# schematic.net
KiCad netlist of a schematic drawn in EAGLE
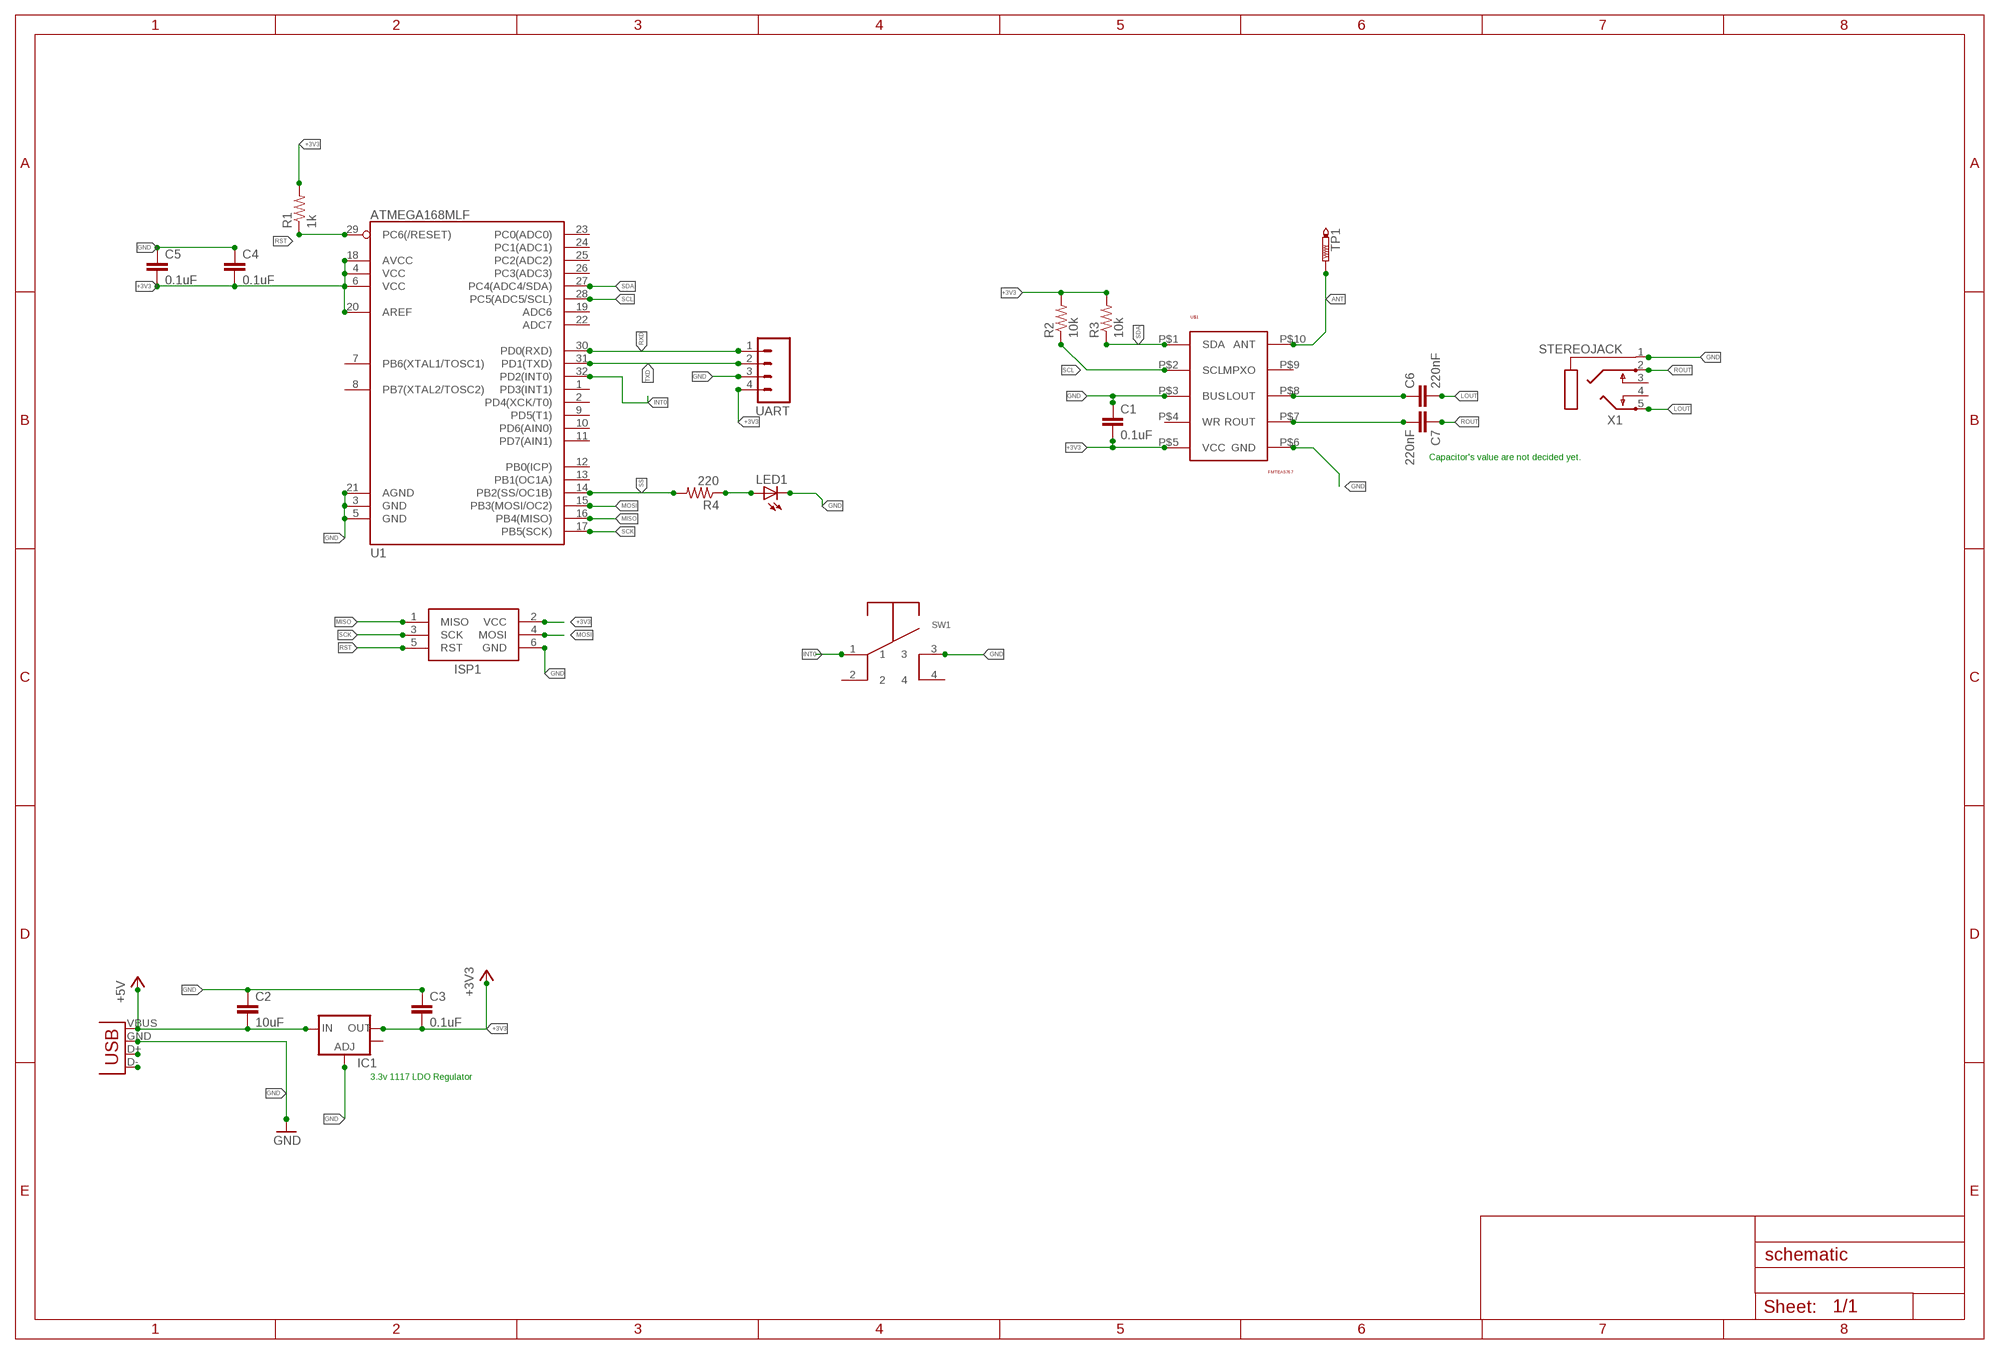
[diagram p0: schematic, sheet 1]

(export (version "E")
  (design (tool "Eeschema 10.0.6"))
  (components
    (comp (ref "C1")
      (value "0.1uF")
      (footprint "eagle-import:0402-CAP")
      (libsource (lib "eagle-import") (part "CAP0402-CAP"))
    )
    (comp (ref "C2")
      (value "10uF")
      (footprint "eagle-import:0402-CAP")
      (libsource (lib "eagle-import") (part "CAP0402-CAP"))
    )
    (comp (ref "C3")
      (value "0.1uF")
      (footprint "eagle-import:0402-CAP")
      (libsource (lib "eagle-import") (part "CAP0402-CAP"))
    )
    (comp (ref "C4")
      (value "0.1uF")
      (footprint "eagle-import:0402-CAP")
      (libsource (lib "eagle-import") (part "CAP0402-CAP"))
    )
    (comp (ref "C5")
      (value "0.1uF")
      (footprint "eagle-import:0402-CAP")
      (libsource (lib "eagle-import") (part "CAP0402-CAP"))
    )
    (comp (ref "C6")
      (value "220nF")
      (footprint "eagle-import:0402-CAP")
      (libsource (lib "eagle-import") (part "CAP0402-CAP"))
    )
    (comp (ref "C7")
      (value "220nF")
      (footprint "eagle-import:0402-CAP")
      (libsource (lib "eagle-import") (part "CAP0402-CAP"))
    )
    (comp (ref "IC1")
      (value "V_REG_LM1117SOT223")
      (footprint "eagle-import:SOT223")
      (libsource (lib "eagle-import") (part "V_REG_LM1117SOT223"))
    )
    (comp (ref "ISP1")
      (value "AVRISP-6")
      (footprint "eagle-import:AVRISP")
      (libsource (lib "eagle-import") (part "AVRISP-6"))
    )
    (comp (ref "JP1")
      (value "USB-A-H")
      (footprint "eagle-import:USB-A-H")
      (libsource (lib "eagle-import") (part "USB-A-H"))
    )
    (comp (ref "LED1")
      (value "LEDCHIPLED_0603")
      (footprint "eagle-import:CHIPLED_0603")
      (libsource (lib "eagle-import") (part "LEDCHIPLED_0603"))
    )
    (comp (ref "R1")
      (value "1k")
      (footprint "eagle-import:0402-RES")
      (libsource (lib "eagle-import") (part "RESISTOR0402-RES"))
    )
    (comp (ref "R2")
      (value "10k")
      (footprint "eagle-import:0402-RES")
      (libsource (lib "eagle-import") (part "RESISTOR0402-RES"))
    )
    (comp (ref "R3")
      (value "10k")
      (footprint "eagle-import:0402-RES")
      (libsource (lib "eagle-import") (part "RESISTOR0402-RES"))
    )
    (comp (ref "R4")
      (value "220")
      (footprint "eagle-import:0402-RES")
      (libsource (lib "eagle-import") (part "RESISTOR0402-RES"))
    )
    (comp (ref "SW1")
      (value "TAC-SOFT")
      (footprint "eagle-import:SWITCH_SMD")
      (libsource (lib "eagle-import") (part "TAC-SOFT"))
    )
    (comp (ref "TP1")
      (value "PTR1TP20SQ")
      (footprint "eagle-import:TP20SQ")
      (libsource (lib "eagle-import") (part "PTR1TP20SQ"))
    )
    (comp (ref "U$1")
      (value "FMTEA5767")
      (footprint "eagle-import:FMTEA5767")
      (libsource (lib "eagle-import") (part "FMTEA5767"))
    )
    (comp (ref "U1")
      (value "ATMEGA168MLF")
      (footprint "eagle-import:MLF32")
      (libsource (lib "eagle-import") (part "ATMEGA168MLF"))
    )
    (comp (ref "UART")
      (value "M04PTH")
      (footprint "eagle-import:1X04")
      (libsource (lib "eagle-import") (part "M04PTH"))
    )
    (comp (ref "X1")
      (value "STEREOJACK")
      (footprint "eagle-import:STX3100")
      (libsource (lib "eagle-import") (part "STEREOJACK"))
    )
  )
  (nets
    (net (code "1") (name "+3V3") (class "Default")
      (node (ref "C1") (pin "2") (pinfunction "2_2") (pintype "passive"))
      (node (ref "C3") (pin "2") (pinfunction "2_2") (pintype "passive"))
      (node (ref "C4") (pin "2") (pinfunction "2_2") (pintype "passive"))
      (node (ref "C5") (pin "2") (pinfunction "2_2") (pintype "passive"))
      (node (ref "IC1") (pin "2") (pinfunction "OUT_2") (pintype "output"))
      (node (ref "ISP1") (pin "2") (pinfunction "VCC_2") (pintype "power_in"))
      (node (ref "R1") (pin "2") (pinfunction "2_2") (pintype "passive"))
      (node (ref "R2") (pin "2") (pinfunction "2_2") (pintype "passive"))
      (node (ref "R3") (pin "2") (pinfunction "2_2") (pintype "passive"))
      (node (ref "U$1") (pin "P$5") (pinfunction "VCC_P$5") (pintype "bidirectional"))
      (node (ref "U1") (pin "18") (pinfunction "AVCC_18") (pintype "bidirectional"))
      (node (ref "U1") (pin "20") (pinfunction "AREF_20") (pintype "bidirectional"))
      (node (ref "U1") (pin "4") (pinfunction "VCC_4") (pintype "bidirectional"))
      (node (ref "U1") (pin "6") (pinfunction "VCC_6") (pintype "bidirectional"))
      (node (ref "UART") (pin "4") (pinfunction "4_4") (pintype "passive"))
    )
    (net (code "2") (name "+5V") (class "Default")
      (node (ref "C2") (pin "2") (pinfunction "2_2") (pintype "passive"))
      (node (ref "IC1") (pin "3") (pinfunction "IN_3") (pintype "input"))
      (node (ref "JP1") (pin "VBUS") (pinfunction "GND_VBUS") (pintype "bidirectional"))
    )
    (net (code "3") (name "ANT") (class "Default")
      (node (ref "TP1") (pin "TP") (pinfunction "TP_TP") (pintype "input"))
      (node (ref "U$1") (pin "P$10") (pinfunction "ANT_P$10") (pintype "bidirectional"))
    )
    (net (code "4") (name "GND") (class "Default")
      (node (ref "C1") (pin "1") (pinfunction "1_1") (pintype "passive"))
      (node (ref "C2") (pin "1") (pinfunction "1_1") (pintype "passive"))
      (node (ref "C3") (pin "1") (pinfunction "1_1") (pintype "passive"))
      (node (ref "C4") (pin "1") (pinfunction "1_1") (pintype "passive"))
      (node (ref "C5") (pin "1") (pinfunction "1_1") (pintype "passive"))
      (node (ref "IC1") (pin "1") (pinfunction "ADJ_1") (pintype "input"))
      (node (ref "ISP1") (pin "6") (pinfunction "GND_6") (pintype "power_in"))
      (node (ref "JP1") (pin "GND") (pinfunction "VBUS_GND") (pintype "bidirectional"))
      (node (ref "LED1") (pin "C") (pinfunction "C_C") (pintype "passive"))
      (node (ref "SW1") (pin "3") (pinfunction "3_3") (pintype "bidirectional"))
      (node (ref "U$1") (pin "P$3") (pinfunction "BUS_P$3") (pintype "bidirectional"))
      (node (ref "U$1") (pin "P$6") (pinfunction "GND_P$6") (pintype "bidirectional"))
      (node (ref "U1") (pin "21") (pinfunction "AGND_21") (pintype "bidirectional"))
      (node (ref "U1") (pin "3") (pinfunction "GND_3") (pintype "bidirectional"))
      (node (ref "U1") (pin "5") (pinfunction "GND_5") (pintype "bidirectional"))
      (node (ref "UART") (pin "3") (pinfunction "3_3") (pintype "passive"))
      (node (ref "X1") (pin "1") (pinfunction "1_1") (pintype "passive"))
    )
    (net (code "5") (name "INT0") (class "Default")
      (node (ref "SW1") (pin "1") (pinfunction "1_1") (pintype "bidirectional"))
      (node (ref "U1") (pin "32") (pinfunction "PD2(INT0)_32") (pintype "bidirectional"))
    )
    (net (code "6") (name "LOUT") (class "Default")
      (node (ref "C6") (pin "2") (pinfunction "2_2") (pintype "passive"))
      (node (ref "X1") (pin "5") (pinfunction "5_5") (pintype "passive"))
    )
    (net (code "7") (name "MISO") (class "Default")
      (node (ref "ISP1") (pin "1") (pinfunction "MISO_1") (pintype "input"))
      (node (ref "U1") (pin "16") (pinfunction "PB4(MISO)_16") (pintype "bidirectional"))
    )
    (net (code "8") (name "MOSI") (class "Default")
      (node (ref "ISP1") (pin "4") (pinfunction "MOSI_4") (pintype "output"))
      (node (ref "U1") (pin "15") (pinfunction "PB3(MOSI/OC2)_15") (pintype "bidirectional"))
    )
    (net (code "9") (name "Net-(LED1-PadA)") (class "Default")
      (node (ref "LED1") (pin "A") (pinfunction "A_A") (pintype "passive"))
      (node (ref "R4") (pin "1") (pinfunction "1_1") (pintype "passive"))
    )
    (net (code "10") (name "Net-(U$1-LOUT)") (class "Default")
      (node (ref "C6") (pin "1") (pinfunction "1_1") (pintype "passive"))
      (node (ref "U$1") (pin "P$8") (pinfunction "LOUT_P$8") (pintype "bidirectional"))
    )
    (net (code "11") (name "Net-(U$1-ROUT)") (class "Default")
      (node (ref "C7") (pin "2") (pinfunction "2_2") (pintype "passive"))
      (node (ref "U$1") (pin "P$7") (pinfunction "ROUT_P$7") (pintype "bidirectional"))
    )
    (net (code "12") (name "ROUT") (class "Default")
      (node (ref "C7") (pin "1") (pinfunction "1_1") (pintype "passive"))
      (node (ref "X1") (pin "2") (pinfunction "2_2") (pintype "passive"))
    )
    (net (code "13") (name "RST") (class "Default")
      (node (ref "ISP1") (pin "5") (pinfunction "RST_5") (pintype "output"))
      (node (ref "R1") (pin "1") (pinfunction "1_1") (pintype "passive"))
      (node (ref "U1") (pin "29") (pinfunction "PC6(/RESET)_29") (pintype "bidirectional"))
    )
    (net (code "14") (name "RXD") (class "Default")
      (node (ref "U1") (pin "30") (pinfunction "PD0(RXD)_30") (pintype "bidirectional"))
      (node (ref "UART") (pin "1") (pinfunction "1_1") (pintype "passive"))
    )
    (net (code "15") (name "SCK") (class "Default")
      (node (ref "ISP1") (pin "3") (pinfunction "SCK_3") (pintype "output"))
      (node (ref "U1") (pin "17") (pinfunction "PB5(SCK)_17") (pintype "bidirectional"))
    )
    (net (code "16") (name "SCL") (class "Default")
      (node (ref "R2") (pin "1") (pinfunction "1_1") (pintype "passive"))
      (node (ref "U$1") (pin "P$2") (pinfunction "SCL_P$2") (pintype "bidirectional"))
      (node (ref "U1") (pin "28") (pinfunction "PC5(ADC5/SCL)_28") (pintype "bidirectional"))
    )
    (net (code "17") (name "SDA") (class "Default")
      (node (ref "R3") (pin "1") (pinfunction "1_1") (pintype "passive"))
      (node (ref "U$1") (pin "P$1") (pinfunction "SDA_P$1") (pintype "bidirectional"))
      (node (ref "U1") (pin "27") (pinfunction "PC4(ADC4/SDA)_27") (pintype "bidirectional"))
    )
    (net (code "18") (name "SS") (class "Default")
      (node (ref "R4") (pin "2") (pinfunction "2_2") (pintype "passive"))
      (node (ref "U1") (pin "14") (pinfunction "PB2(SS/OC1B)_14") (pintype "bidirectional"))
    )
    (net (code "19") (name "TXD") (class "Default")
      (node (ref "U1") (pin "31") (pinfunction "PD1(TXD)_31") (pintype "bidirectional"))
      (node (ref "UART") (pin "2") (pinfunction "2_2") (pintype "passive"))
    )
    (net (code "20") (name "unconnected-(IC1-OUT-Pad4)") (class "Default")
      (node (ref "IC1") (pin "4") (pinfunction "OUT_4") (pintype "output"))
    )
    (net (code "21") (name "unconnected-(JP1-D+-PadD-)") (class "Default")
      (node (ref "JP1") (pin "D-") (pinfunction "D+_D-") (pintype "bidirectional"))
    )
    (net (code "22") (name "unconnected-(JP1-D--PadD+)") (class "Default")
      (node (ref "JP1") (pin "D+") (pinfunction "D-_D+") (pintype "bidirectional"))
    )
    (net (code "23") (name "unconnected-(SW1-Pad2)") (class "Default")
      (node (ref "SW1") (pin "2") (pinfunction "2_2") (pintype "bidirectional"))
    )
    (net (code "24") (name "unconnected-(SW1-Pad4)") (class "Default")
      (node (ref "SW1") (pin "4") (pinfunction "4_4") (pintype "bidirectional"))
    )
    (net (code "25") (name "unconnected-(U$1-MPXO-PadP$9)") (class "Default")
      (node (ref "U$1") (pin "P$9") (pinfunction "MPXO_P$9") (pintype "bidirectional"))
    )
    (net (code "26") (name "unconnected-(U$1-WR-PadP$4)") (class "Default")
      (node (ref "U$1") (pin "P$4") (pinfunction "WR_P$4") (pintype "bidirectional"))
    )
    (net (code "27") (name "unconnected-(U1-ADC6-Pad19)") (class "Default")
      (node (ref "U1") (pin "19") (pinfunction "ADC6_19") (pintype "bidirectional"))
    )
    (net (code "28") (name "unconnected-(U1-ADC7-Pad22)") (class "Default")
      (node (ref "U1") (pin "22") (pinfunction "ADC7_22") (pintype "bidirectional"))
    )
    (net (code "29") (name "unconnected-(U1-PB0(ICP)-Pad12)") (class "Default")
      (node (ref "U1") (pin "12") (pinfunction "PB0(ICP)_12") (pintype "bidirectional"))
    )
    (net (code "30") (name "unconnected-(U1-PB1(OC1A)-Pad13)") (class "Default")
      (node (ref "U1") (pin "13") (pinfunction "PB1(OC1A)_13") (pintype "bidirectional"))
    )
    (net (code "31") (name "unconnected-(U1-PB6(XTAL1{slash}TOSC1)-Pad7)") (class "Default")
      (node (ref "U1") (pin "7") (pinfunction "PB6(XTAL1/TOSC1)_7") (pintype "bidirectional"))
    )
    (net (code "32") (name "unconnected-(U1-PB7(XTAL2{slash}TOSC2)-Pad8)") (class "Default")
      (node (ref "U1") (pin "8") (pinfunction "PB7(XTAL2/TOSC2)_8") (pintype "bidirectional"))
    )
    (net (code "33") (name "unconnected-(U1-PC0(ADC0)-Pad23)") (class "Default")
      (node (ref "U1") (pin "23") (pinfunction "PC0(ADC0)_23") (pintype "bidirectional"))
    )
    (net (code "34") (name "unconnected-(U1-PC1(ADC1)-Pad24)") (class "Default")
      (node (ref "U1") (pin "24") (pinfunction "PC1(ADC1)_24") (pintype "bidirectional"))
    )
    (net (code "35") (name "unconnected-(U1-PC2(ADC2)-Pad25)") (class "Default")
      (node (ref "U1") (pin "25") (pinfunction "PC2(ADC2)_25") (pintype "bidirectional"))
    )
    (net (code "36") (name "unconnected-(U1-PC3(ADC3)-Pad26)") (class "Default")
      (node (ref "U1") (pin "26") (pinfunction "PC3(ADC3)_26") (pintype "bidirectional"))
    )
    (net (code "37") (name "unconnected-(U1-PD3(INT1)-Pad1)") (class "Default")
      (node (ref "U1") (pin "1") (pinfunction "PD3(INT1)_1") (pintype "bidirectional"))
    )
    (net (code "38") (name "unconnected-(U1-PD4(XCK{slash}T0)-Pad2)") (class "Default")
      (node (ref "U1") (pin "2") (pinfunction "PD4(XCK/T0)_2") (pintype "bidirectional"))
    )
    (net (code "39") (name "unconnected-(U1-PD5(T1)-Pad9)") (class "Default")
      (node (ref "U1") (pin "9") (pinfunction "PD5(T1)_9") (pintype "bidirectional"))
    )
    (net (code "40") (name "unconnected-(U1-PD6(AIN0)-Pad10)") (class "Default")
      (node (ref "U1") (pin "10") (pinfunction "PD6(AIN0)_10") (pintype "bidirectional"))
    )
    (net (code "41") (name "unconnected-(U1-PD7(AIN1)-Pad11)") (class "Default")
      (node (ref "U1") (pin "11") (pinfunction "PD7(AIN1)_11") (pintype "bidirectional"))
    )
    (net (code "42") (name "unconnected-(X1-Pad3)") (class "Default")
      (node (ref "X1") (pin "3") (pinfunction "3_3") (pintype "passive"))
    )
    (net (code "43") (name "unconnected-(X1-Pad4)") (class "Default")
      (node (ref "X1") (pin "4") (pinfunction "4_4") (pintype "passive"))
    )
  )
)
